# 5V_Digital_Out.net
KiCad netlist of a schematic drawn in Altium Designer
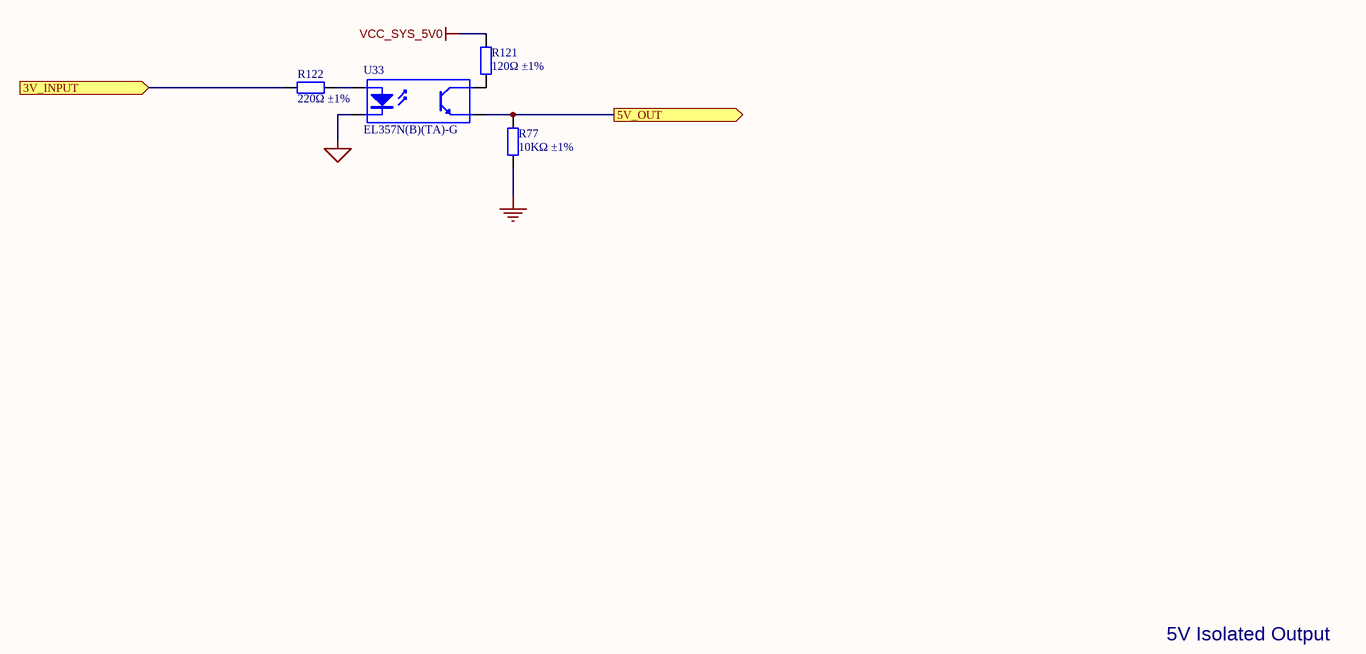
[diagram p0: 5V_Digital_Out.SchDoc]

(export (version "E")
  (design (tool "Eeschema 10.0.6"))
  (components
    (comp (ref "R77")
      (value "10KΩ ±1%")
      (footprint "0402_R")
      (description "Chip resistor")
      (fields
        (field (name "MANUFACTURER") "Uniroyal Elec")
        (field (name "MANUFACTURER PART NUMBER") "0402WGF1002TCE")
      )
      (libsource (lib "Sienci_Labs") (part "0402 10K (1002) 1%"))
    )
    (comp (ref "R121")
      (value "120Ω ±1%")
      (footprint "0402_R")
      (description "Chip resistor")
      (fields
        (field (name "MANUFACTURER") "Uniroyal Elec")
        (field (name "MANUFACTURER PART NUMBER") "0402WGF1200TCE")
      )
      (libsource (lib "RES") (part "0402 120R (1200) 1%"))
    )
    (comp (ref "R122")
      (value "220Ω ±1%")
      (footprint "0402_R")
      (description "Chip resistor")
      (fields
        (field (name "MANUFACTURER") "Uniroyal Elec")
        (field (name "MANUFACTURER PART NUMBER") "0402WGF2200TCE")
      )
      (libsource (lib "RES") (part "0402 220R (2200) 1%"))
    )
    (comp (ref "U33")
      (value "EL357N(B)(TA)-G")
      (footprint "Miscellaneous Devices LC:SOP-4_P2.54")
      (description "Optocoupler SOP-4, EL357N(B)(TA)-G, Everlight Electronics")
      (fields (field (name "MANUFACTURER") "Everlight"))
      (libsource (lib "Sienci_Labs") (part "EL357N(B)(TA)-G_[C6649]"))
    )
  )
  (nets
    (net (code "1") (name "/3V_INPUT") (class "Default")
      (node (ref "R122") (pin "1") (pinfunction "1_1") (pintype "passive"))
    )
    (net (code "2") (name "/5V_OUT") (class "Default")
      (node (ref "R77") (pin "2") (pinfunction "2_2") (pintype "passive"))
      (node (ref "U33") (pin "3") (pinfunction "E_3") (pintype "passive"))
    )
    (net (code "3") (name "GND") (class "Default")
      (node (ref "R77") (pin "1") (pinfunction "1_1") (pintype "passive"))
    )
    (net (code "4") (name "MCU_GND") (class "Default")
      (node (ref "U33") (pin "2") (pinfunction "K_2") (pintype "passive"))
    )
    (net (code "5") (name "Net-(U33-A)") (class "Default")
      (node (ref "R122") (pin "2") (pinfunction "2_2") (pintype "passive"))
      (node (ref "U33") (pin "1") (pinfunction "A_1") (pintype "passive"))
    )
    (net (code "6") (name "Net-(U33-C)") (class "Default")
      (node (ref "R121") (pin "2") (pinfunction "2_2") (pintype "passive"))
      (node (ref "U33") (pin "4") (pinfunction "C_4") (pintype "passive"))
    )
    (net (code "7") (name "VCC_SYS_5V0") (class "Default")
      (node (ref "R121") (pin "1") (pinfunction "1_1") (pintype "passive"))
    )
  )
)
